# isa_cvx.net
KiCad netlist of a schematic drawn in EAGLE
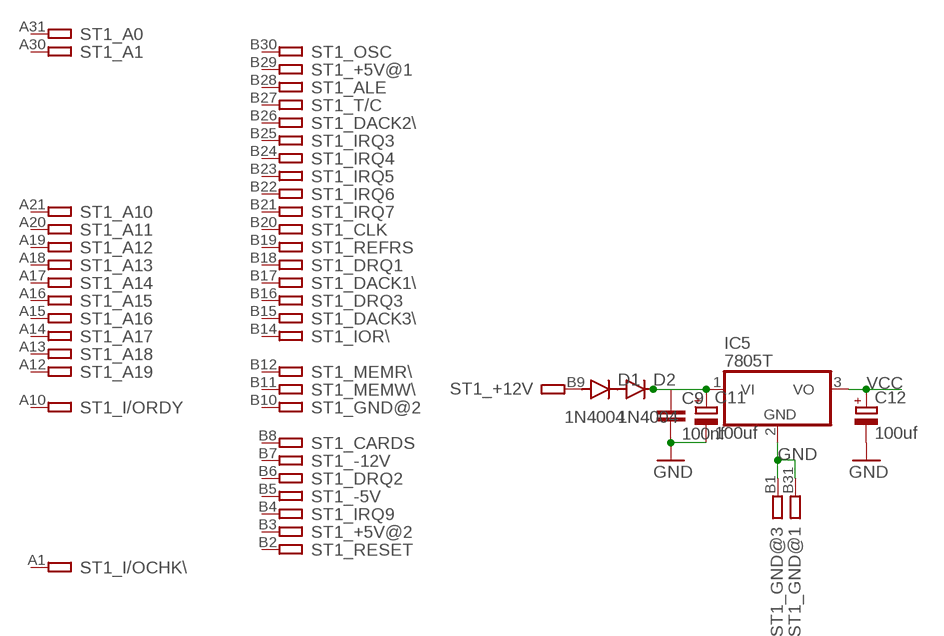
[diagram p0: schematic, sheet 1, part 1 of 2]
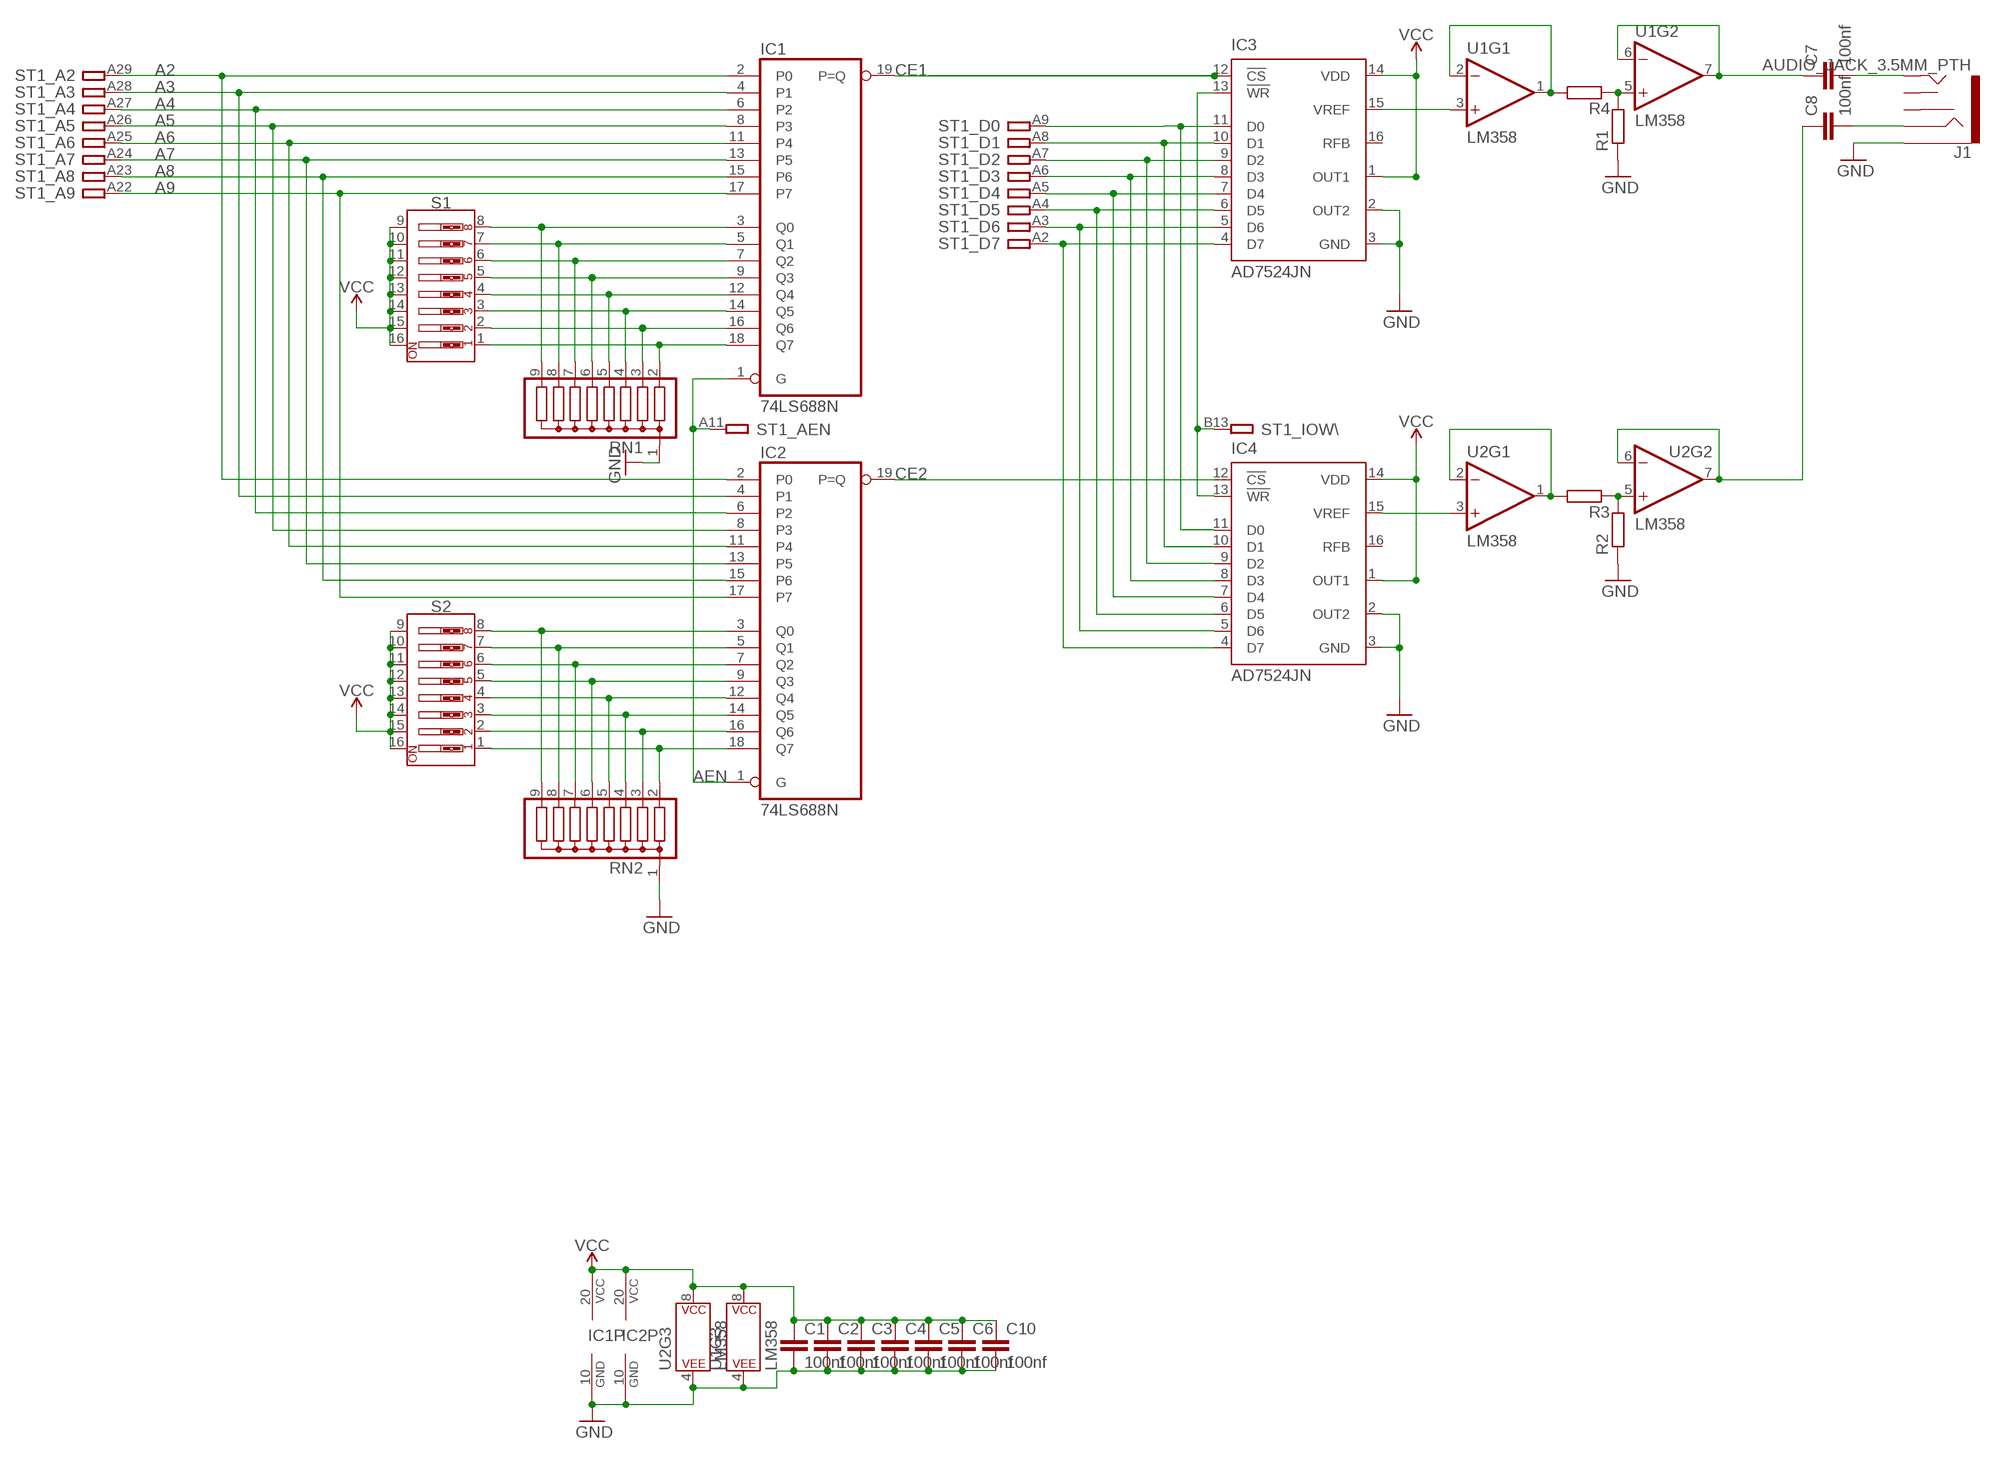
[diagram p1: schematic, sheet 1, part 2 of 2]

(export (version "E")
  (design (tool "Eeschema 10.0.6"))
  (components
    (comp (ref "C1")
      (value "100nf")
      (footprint "eagle-import:C2.5-2")
      (libsource (lib "eagle-import") (part "C2.5/2"))
    )
    (comp (ref "C2")
      (value "100nf")
      (footprint "eagle-import:C2.5-2")
      (libsource (lib "eagle-import") (part "C2.5/2"))
    )
    (comp (ref "C3")
      (value "100nf")
      (footprint "eagle-import:C2.5-2")
      (libsource (lib "eagle-import") (part "C2.5/2"))
    )
    (comp (ref "C4")
      (value "100nf")
      (footprint "eagle-import:C2.5-2")
      (libsource (lib "eagle-import") (part "C2.5/2"))
    )
    (comp (ref "C5")
      (value "100nf")
      (footprint "eagle-import:C2.5-2")
      (libsource (lib "eagle-import") (part "C2.5/2"))
    )
    (comp (ref "C6")
      (value "100nf")
      (footprint "eagle-import:C2.5-2")
      (libsource (lib "eagle-import") (part "C2.5/2"))
    )
    (comp (ref "C7")
      (value "100nf")
      (footprint "eagle-import:C2.5-2")
      (libsource (lib "eagle-import") (part "C2.5/2"))
    )
    (comp (ref "C8")
      (value "100nf")
      (footprint "eagle-import:C2.5-2")
      (libsource (lib "eagle-import") (part "C2.5/2"))
    )
    (comp (ref "C9")
      (value "100nf")
      (footprint "eagle-import:C2.5-2")
      (libsource (lib "eagle-import") (part "C2.5/2"))
    )
    (comp (ref "C10")
      (value "100nf")
      (footprint "eagle-import:C2.5-2")
      (libsource (lib "eagle-import") (part "C2.5/2"))
    )
    (comp (ref "C11")
      (value "100uf")
      (footprint "eagle-import:E2,5-5")
      (libsource (lib "eagle-import") (part "CPOL-EUE2.5-5"))
    )
    (comp (ref "C12")
      (value "100uf")
      (footprint "eagle-import:E2,5-5")
      (libsource (lib "eagle-import") (part "CPOL-EUE2.5-5"))
    )
    (comp (ref "D1")
      (value "1N4004")
      (footprint "eagle-import:DO41-10")
      (libsource (lib "eagle-import") (part "1N4004"))
    )
    (comp (ref "D2")
      (value "1N4004")
      (footprint "eagle-import:DO41-10")
      (libsource (lib "eagle-import") (part "1N4004"))
    )
    (comp (ref "IC1")
      (value "74LS688N")
      (footprint "eagle-import:DIL20")
      (libsource (lib "eagle-import") (part "74688NLS"))
    )
    (comp (ref "IC2")
      (value "74LS688N")
      (footprint "eagle-import:DIL20")
      (libsource (lib "eagle-import") (part "74688NLS"))
    )
    (comp (ref "IC3")
      (value "AD7524JN")
      (footprint "eagle-import:DIL16")
      (fields (field (name "MF") "ALTERA CORPORATION") (field (name "MPN") "AD7524JNZ"))
      (libsource (lib "eagle-import") (part "AD7524NJ"))
    )
    (comp (ref "IC4")
      (value "AD7524JN")
      (footprint "eagle-import:DIL16")
      (fields (field (name "MF") "ALTERA CORPORATION") (field (name "MPN") "AD7524JNZ"))
      (libsource (lib "eagle-import") (part "AD7524NJ"))
    )
    (comp (ref "IC5")
      (value "7805T")
      (footprint "eagle-import:TO220H")
      (libsource (lib "eagle-import") (part "78T05"))
    )
    (comp (ref "J1")
      (value "AUDIO_JACK_3.5MM_PTH")
      (footprint "eagle-import:AUDIO-JACK")
      (libsource (lib "eagle-import") (part "AUDIO_JACK_3.5MM_PTH"))
    )
    (comp (ref "R1")
      (value "R-EU_0207/10")
      (footprint "eagle-import:0207_10")
      (libsource (lib "eagle-import") (part "R-EU_0207/10"))
    )
    (comp (ref "R2")
      (value "R-EU_0207/10")
      (footprint "eagle-import:0207_10")
      (libsource (lib "eagle-import") (part "R-EU_0207/10"))
    )
    (comp (ref "R3")
      (value "R-EU_0207/10")
      (footprint "eagle-import:0207_10")
      (libsource (lib "eagle-import") (part "R-EU_0207/10"))
    )
    (comp (ref "R4")
      (value "R-EU_0207/10")
      (footprint "eagle-import:0207_10")
      (libsource (lib "eagle-import") (part "R-EU_0207/10"))
    )
    (comp (ref "RN1")
      (value "G08R")
      (footprint "eagle-import:SIL9")
      (libsource (lib "eagle-import") (part "G08R"))
    )
    (comp (ref "RN2")
      (value "G08R")
      (footprint "eagle-import:SIL9")
      (libsource (lib "eagle-import") (part "G08R"))
    )
    (comp (ref "S1")
      (value "DIP-08-PTH")
      (footprint "eagle-import:DIPSWITCH-08")
      (libsource (lib "eagle-import") (part "DIP-08-PTH"))
    )
    (comp (ref "S2")
      (value "DIP-08-PTH")
      (footprint "eagle-import:DIPSWITCH-08")
      (libsource (lib "eagle-import") (part "DIP-08-PTH"))
    )
    (comp (ref "ST1")
      (value "IBM8BIT")
      (footprint "eagle-import:IBM8BIT")
      (libsource (lib "eagle-import") (part "IBM8BIT"))
    )
    (comp (ref "U1")
      (value "LM358")
      (footprint "eagle-import:DIP08")
      (libsource (lib "eagle-import") (part "LM358"))
    )
    (comp (ref "U2")
      (value "LM358")
      (footprint "eagle-import:DIP08")
      (libsource (lib "eagle-import") (part "LM358"))
    )
  )
  (nets
    (net (code "1") (name "/A2") (class "Default")
      (node (ref "IC1") (pin "2") (pinfunction "P0_2") (pintype "input"))
      (node (ref "IC2") (pin "2") (pinfunction "P0_2") (pintype "input"))
      (node (ref "ST1") (pin "A29") (pinfunction "P_A29") (pintype "bidirectional"))
    )
    (net (code "2") (name "/A3") (class "Default")
      (node (ref "IC1") (pin "4") (pinfunction "P1_4") (pintype "input"))
      (node (ref "IC2") (pin "4") (pinfunction "P1_4") (pintype "input"))
      (node (ref "ST1") (pin "A28") (pinfunction "P_A28") (pintype "bidirectional"))
    )
    (net (code "3") (name "/A4") (class "Default")
      (node (ref "IC1") (pin "6") (pinfunction "P2_6") (pintype "input"))
      (node (ref "IC2") (pin "6") (pinfunction "P2_6") (pintype "input"))
      (node (ref "ST1") (pin "A27") (pinfunction "P_A27") (pintype "bidirectional"))
    )
    (net (code "4") (name "/A5") (class "Default")
      (node (ref "IC1") (pin "8") (pinfunction "P3_8") (pintype "input"))
      (node (ref "IC2") (pin "8") (pinfunction "P3_8") (pintype "input"))
      (node (ref "ST1") (pin "A26") (pinfunction "P_A26") (pintype "bidirectional"))
    )
    (net (code "5") (name "/A6") (class "Default")
      (node (ref "IC1") (pin "11") (pinfunction "P4_11") (pintype "input"))
      (node (ref "IC2") (pin "11") (pinfunction "P4_11") (pintype "input"))
      (node (ref "ST1") (pin "A25") (pinfunction "P_A25") (pintype "bidirectional"))
    )
    (net (code "6") (name "/A7") (class "Default")
      (node (ref "IC1") (pin "13") (pinfunction "P5_13") (pintype "input"))
      (node (ref "IC2") (pin "13") (pinfunction "P5_13") (pintype "input"))
      (node (ref "ST1") (pin "A24") (pinfunction "P_A24") (pintype "bidirectional"))
    )
    (net (code "7") (name "/A8") (class "Default")
      (node (ref "IC1") (pin "15") (pinfunction "P6_15") (pintype "input"))
      (node (ref "IC2") (pin "15") (pinfunction "P6_15") (pintype "input"))
      (node (ref "ST1") (pin "A23") (pinfunction "P_A23") (pintype "bidirectional"))
    )
    (net (code "8") (name "/A9") (class "Default")
      (node (ref "IC1") (pin "17") (pinfunction "P7_17") (pintype "input"))
      (node (ref "IC2") (pin "17") (pinfunction "P7_17") (pintype "input"))
      (node (ref "ST1") (pin "A22") (pinfunction "P_A22") (pintype "bidirectional"))
    )
    (net (code "9") (name "/AEN") (class "Default")
      (node (ref "IC1") (pin "1") (pinfunction "G_1") (pintype "input"))
      (node (ref "IC2") (pin "1") (pinfunction "G_1") (pintype "input"))
      (node (ref "ST1") (pin "A11") (pinfunction "P_A11") (pintype "bidirectional"))
    )
    (net (code "10") (name "/CE1") (class "Default")
      (node (ref "IC1") (pin "19") (pinfunction "P=Q_19") (pintype "output"))
      (node (ref "IC3") (pin "12") (pinfunction "~{CS}_12") (pintype "input"))
    )
    (net (code "11") (name "/CE2") (class "Default")
      (node (ref "IC2") (pin "19") (pinfunction "P=Q_19") (pintype "output"))
      (node (ref "IC4") (pin "12") (pinfunction "~{CS}_12") (pintype "input"))
    )
    (net (code "12") (name "GND") (class "Default")
      (node (ref "C1") (pin "2") (pinfunction "2_2") (pintype "passive"))
      (node (ref "C10") (pin "2") (pinfunction "2_2") (pintype "passive"))
      (node (ref "C11") (pin "-") (pinfunction "-_-") (pintype "passive"))
      (node (ref "C12") (pin "-") (pinfunction "-_-") (pintype "passive"))
      (node (ref "C2") (pin "2") (pinfunction "2_2") (pintype "passive"))
      (node (ref "C3") (pin "2") (pinfunction "2_2") (pintype "passive"))
      (node (ref "C4") (pin "2") (pinfunction "2_2") (pintype "passive"))
      (node (ref "C5") (pin "2") (pinfunction "2_2") (pintype "passive"))
      (node (ref "C6") (pin "2") (pinfunction "2_2") (pintype "passive"))
      (node (ref "C9") (pin "2") (pinfunction "2_2") (pintype "passive"))
      (node (ref "IC1") (pin "10") (pinfunction "GND_10") (pintype "power_in"))
      (node (ref "IC2") (pin "10") (pinfunction "GND_10") (pintype "power_in"))
      (node (ref "IC3") (pin "2") (pinfunction "OUT2_2") (pintype "passive"))
      (node (ref "IC3") (pin "3") (pinfunction "GND_3") (pintype "power_in"))
      (node (ref "IC4") (pin "2") (pinfunction "OUT2_2") (pintype "passive"))
      (node (ref "IC4") (pin "3") (pinfunction "GND_3") (pintype "power_in"))
      (node (ref "IC5") (pin "2") (pinfunction "GND_2") (pintype "passive"))
      (node (ref "J1") (pin "SLEEVE") (pinfunction "SLEEVE_SLEEVE") (pintype "bidirectional"))
      (node (ref "R1") (pin "1") (pinfunction "1_1") (pintype "passive"))
      (node (ref "R2") (pin "1") (pinfunction "1_1") (pintype "passive"))
      (node (ref "RN1") (pin "1") (pinfunction "1_1") (pintype "passive"))
      (node (ref "RN2") (pin "1") (pinfunction "1_1") (pintype "passive"))
      (node (ref "ST1") (pin "B1") (pinfunction "P_B1") (pintype "bidirectional"))
      (node (ref "ST1") (pin "B31") (pinfunction "P_B31") (pintype "bidirectional"))
      (node (ref "U1") (pin "4") (pinfunction "P$V-_4") (pintype "bidirectional"))
      (node (ref "U2") (pin "4") (pinfunction "P$V-_4") (pintype "bidirectional"))
    )
    (net (code "13") (name "Net-(C7-Pad2)") (class "Default")
      (node (ref "C7") (pin "2") (pinfunction "2_2") (pintype "passive"))
      (node (ref "J1") (pin "TIP") (pinfunction "TIP_TIP") (pintype "bidirectional"))
    )
    (net (code "14") (name "Net-(C8-Pad2)") (class "Default")
      (node (ref "C8") (pin "2") (pinfunction "2_2") (pintype "passive"))
      (node (ref "J1") (pin "RING") (pinfunction "RING_RING") (pintype "bidirectional"))
    )
    (net (code "15") (name "Net-(D1-PadC)") (class "Default")
      (node (ref "D1") (pin "C") (pinfunction "C_C") (pintype "passive"))
      (node (ref "D2") (pin "A") (pinfunction "A_A") (pintype "passive"))
    )
    (net (code "16") (name "Net-(IC1A-Q0)") (class "Default")
      (node (ref "IC1") (pin "3") (pinfunction "Q0_3") (pintype "input"))
      (node (ref "RN1") (pin "9") (pinfunction "9_9") (pintype "passive"))
      (node (ref "S1") (pin "8") (pinfunction "8_8") (pintype "passive"))
    )
    (net (code "17") (name "Net-(IC1A-Q1)") (class "Default")
      (node (ref "IC1") (pin "5") (pinfunction "Q1_5") (pintype "input"))
      (node (ref "RN1") (pin "8") (pinfunction "8_8") (pintype "passive"))
      (node (ref "S1") (pin "7") (pinfunction "7_7") (pintype "passive"))
    )
    (net (code "18") (name "Net-(IC1A-Q2)") (class "Default")
      (node (ref "IC1") (pin "7") (pinfunction "Q2_7") (pintype "input"))
      (node (ref "RN1") (pin "7") (pinfunction "7_7") (pintype "passive"))
      (node (ref "S1") (pin "6") (pinfunction "6_6") (pintype "passive"))
    )
    (net (code "19") (name "Net-(IC1A-Q3)") (class "Default")
      (node (ref "IC1") (pin "9") (pinfunction "Q3_9") (pintype "input"))
      (node (ref "RN1") (pin "6") (pinfunction "6_6") (pintype "passive"))
      (node (ref "S1") (pin "5") (pinfunction "5_5") (pintype "passive"))
    )
    (net (code "20") (name "Net-(IC1A-Q4)") (class "Default")
      (node (ref "IC1") (pin "12") (pinfunction "Q4_12") (pintype "input"))
      (node (ref "RN1") (pin "5") (pinfunction "5_5") (pintype "passive"))
      (node (ref "S1") (pin "4") (pinfunction "4_4") (pintype "passive"))
    )
    (net (code "21") (name "Net-(IC1A-Q5)") (class "Default")
      (node (ref "IC1") (pin "14") (pinfunction "Q5_14") (pintype "input"))
      (node (ref "RN1") (pin "4") (pinfunction "4_4") (pintype "passive"))
      (node (ref "S1") (pin "3") (pinfunction "3_3") (pintype "passive"))
    )
    (net (code "22") (name "Net-(IC1A-Q6)") (class "Default")
      (node (ref "IC1") (pin "16") (pinfunction "Q6_16") (pintype "input"))
      (node (ref "RN1") (pin "3") (pinfunction "3_3") (pintype "passive"))
      (node (ref "S1") (pin "2") (pinfunction "2_2") (pintype "passive"))
    )
    (net (code "23") (name "Net-(IC1A-Q7)") (class "Default")
      (node (ref "IC1") (pin "18") (pinfunction "Q7_18") (pintype "input"))
      (node (ref "RN1") (pin "2") (pinfunction "2_2") (pintype "passive"))
      (node (ref "S1") (pin "1") (pinfunction "1_1") (pintype "passive"))
    )
    (net (code "24") (name "Net-(IC2A-Q0)") (class "Default")
      (node (ref "IC2") (pin "3") (pinfunction "Q0_3") (pintype "input"))
      (node (ref "RN2") (pin "9") (pinfunction "9_9") (pintype "passive"))
      (node (ref "S2") (pin "8") (pinfunction "8_8") (pintype "passive"))
    )
    (net (code "25") (name "Net-(IC2A-Q1)") (class "Default")
      (node (ref "IC2") (pin "5") (pinfunction "Q1_5") (pintype "input"))
      (node (ref "RN2") (pin "8") (pinfunction "8_8") (pintype "passive"))
      (node (ref "S2") (pin "7") (pinfunction "7_7") (pintype "passive"))
    )
    (net (code "26") (name "Net-(IC2A-Q2)") (class "Default")
      (node (ref "IC2") (pin "7") (pinfunction "Q2_7") (pintype "input"))
      (node (ref "RN2") (pin "7") (pinfunction "7_7") (pintype "passive"))
      (node (ref "S2") (pin "6") (pinfunction "6_6") (pintype "passive"))
    )
    (net (code "27") (name "Net-(IC2A-Q3)") (class "Default")
      (node (ref "IC2") (pin "9") (pinfunction "Q3_9") (pintype "input"))
      (node (ref "RN2") (pin "6") (pinfunction "6_6") (pintype "passive"))
      (node (ref "S2") (pin "5") (pinfunction "5_5") (pintype "passive"))
    )
    (net (code "28") (name "Net-(IC2A-Q4)") (class "Default")
      (node (ref "IC2") (pin "12") (pinfunction "Q4_12") (pintype "input"))
      (node (ref "RN2") (pin "5") (pinfunction "5_5") (pintype "passive"))
      (node (ref "S2") (pin "4") (pinfunction "4_4") (pintype "passive"))
    )
    (net (code "29") (name "Net-(IC2A-Q5)") (class "Default")
      (node (ref "IC2") (pin "14") (pinfunction "Q5_14") (pintype "input"))
      (node (ref "RN2") (pin "4") (pinfunction "4_4") (pintype "passive"))
      (node (ref "S2") (pin "3") (pinfunction "3_3") (pintype "passive"))
    )
    (net (code "30") (name "Net-(IC2A-Q6)") (class "Default")
      (node (ref "IC2") (pin "16") (pinfunction "Q6_16") (pintype "input"))
      (node (ref "RN2") (pin "3") (pinfunction "3_3") (pintype "passive"))
      (node (ref "S2") (pin "2") (pinfunction "2_2") (pintype "passive"))
    )
    (net (code "31") (name "Net-(IC2A-Q7)") (class "Default")
      (node (ref "IC2") (pin "18") (pinfunction "Q7_18") (pintype "input"))
      (node (ref "RN2") (pin "2") (pinfunction "2_2") (pintype "passive"))
      (node (ref "S2") (pin "1") (pinfunction "1_1") (pintype "passive"))
    )
    (net (code "32") (name "Net-(IC3-D0)") (class "Default")
      (node (ref "IC3") (pin "11") (pinfunction "D0_11") (pintype "input"))
      (node (ref "IC4") (pin "11") (pinfunction "D0_11") (pintype "input"))
      (node (ref "ST1") (pin "A9") (pinfunction "P_A9") (pintype "bidirectional"))
    )
    (net (code "33") (name "Net-(IC3-D1)") (class "Default")
      (node (ref "IC3") (pin "10") (pinfunction "D1_10") (pintype "input"))
      (node (ref "IC4") (pin "10") (pinfunction "D1_10") (pintype "input"))
      (node (ref "ST1") (pin "A8") (pinfunction "P_A8") (pintype "bidirectional"))
    )
    (net (code "34") (name "Net-(IC3-D2)") (class "Default")
      (node (ref "IC3") (pin "9") (pinfunction "D2_9") (pintype "input"))
      (node (ref "IC4") (pin "9") (pinfunction "D2_9") (pintype "input"))
      (node (ref "ST1") (pin "A7") (pinfunction "P_A7") (pintype "bidirectional"))
    )
    (net (code "35") (name "Net-(IC3-D3)") (class "Default")
      (node (ref "IC3") (pin "8") (pinfunction "D3_8") (pintype "input"))
      (node (ref "IC4") (pin "8") (pinfunction "D3_8") (pintype "input"))
      (node (ref "ST1") (pin "A6") (pinfunction "P_A6") (pintype "bidirectional"))
    )
    (net (code "36") (name "Net-(IC3-D4)") (class "Default")
      (node (ref "IC3") (pin "7") (pinfunction "D4_7") (pintype "input"))
      (node (ref "IC4") (pin "7") (pinfunction "D4_7") (pintype "input"))
      (node (ref "ST1") (pin "A5") (pinfunction "P_A5") (pintype "bidirectional"))
    )
    (net (code "37") (name "Net-(IC3-D5)") (class "Default")
      (node (ref "IC3") (pin "6") (pinfunction "D5_6") (pintype "input"))
      (node (ref "IC4") (pin "6") (pinfunction "D5_6") (pintype "input"))
      (node (ref "ST1") (pin "A4") (pinfunction "P_A4") (pintype "bidirectional"))
    )
    (net (code "38") (name "Net-(IC3-D6)") (class "Default")
      (node (ref "IC3") (pin "5") (pinfunction "D6_5") (pintype "input"))
      (node (ref "IC4") (pin "5") (pinfunction "D6_5") (pintype "input"))
      (node (ref "ST1") (pin "A3") (pinfunction "P_A3") (pintype "bidirectional"))
    )
    (net (code "39") (name "Net-(IC3-D7)") (class "Default")
      (node (ref "IC3") (pin "4") (pinfunction "D7_4") (pintype "input"))
      (node (ref "IC4") (pin "4") (pinfunction "D7_4") (pintype "input"))
      (node (ref "ST1") (pin "A2") (pinfunction "P_A2") (pintype "bidirectional"))
    )
    (net (code "40") (name "Net-(IC3-VREF)") (class "Default")
      (node (ref "IC3") (pin "15") (pinfunction "VREF_15") (pintype "input"))
      (node (ref "U1") (pin "3") (pinfunction "+IN_3") (pintype "input"))
    )
    (net (code "41") (name "Net-(IC3-~{WR})") (class "Default")
      (node (ref "IC3") (pin "13") (pinfunction "~{WR}_13") (pintype "input"))
      (node (ref "IC4") (pin "13") (pinfunction "~{WR}_13") (pintype "input"))
      (node (ref "ST1") (pin "B13") (pinfunction "P_B13") (pintype "bidirectional"))
    )
    (net (code "42") (name "Net-(IC4-VREF)") (class "Default")
      (node (ref "IC4") (pin "15") (pinfunction "VREF_15") (pintype "input"))
      (node (ref "U2") (pin "3") (pinfunction "+IN_3") (pintype "input"))
    )
    (net (code "43") (name "Net-(IC5-VI)") (class "Default")
      (node (ref "C11") (pin "+") (pinfunction "+_+") (pintype "passive"))
      (node (ref "C9") (pin "1") (pinfunction "1_1") (pintype "passive"))
      (node (ref "D2") (pin "C") (pinfunction "C_C") (pintype "passive"))
      (node (ref "IC5") (pin "1") (pinfunction "VI_1") (pintype "input"))
    )
    (net (code "44") (name "Net-(ST1A-P)") (class "Default")
      (node (ref "D1") (pin "A") (pinfunction "A_A") (pintype "passive"))
      (node (ref "ST1") (pin "B9") (pinfunction "P_B9") (pintype "bidirectional"))
    )
    (net (code "45") (name "Net-(U1A--IN)") (class "Default")
      (node (ref "R4") (pin "2") (pinfunction "2_2") (pintype "passive"))
      (node (ref "U1") (pin "1") (pinfunction "OUT_1") (pintype "output"))
      (node (ref "U1") (pin "2") (pinfunction "-IN_2") (pintype "input"))
    )
    (net (code "46") (name "Net-(U1B-+IN)") (class "Default")
      (node (ref "R1") (pin "2") (pinfunction "2_2") (pintype "passive"))
      (node (ref "R4") (pin "1") (pinfunction "1_1") (pintype "passive"))
      (node (ref "U1") (pin "5") (pinfunction "+IN_5") (pintype "input"))
    )
    (net (code "47") (name "Net-(U1B--IN)") (class "Default")
      (node (ref "C7") (pin "1") (pinfunction "1_1") (pintype "passive"))
      (node (ref "U1") (pin "6") (pinfunction "-IN_6") (pintype "input"))
      (node (ref "U1") (pin "7") (pinfunction "OUT_7") (pintype "output"))
    )
    (net (code "48") (name "Net-(U2A--IN)") (class "Default")
      (node (ref "R3") (pin "2") (pinfunction "2_2") (pintype "passive"))
      (node (ref "U2") (pin "1") (pinfunction "OUT_1") (pintype "output"))
      (node (ref "U2") (pin "2") (pinfunction "-IN_2") (pintype "input"))
    )
    (net (code "49") (name "Net-(U2B-+IN)") (class "Default")
      (node (ref "R2") (pin "2") (pinfunction "2_2") (pintype "passive"))
      (node (ref "R3") (pin "1") (pinfunction "1_1") (pintype "passive"))
      (node (ref "U2") (pin "5") (pinfunction "+IN_5") (pintype "input"))
    )
    (net (code "50") (name "Net-(U2B--IN)") (class "Default")
      (node (ref "C8") (pin "1") (pinfunction "1_1") (pintype "passive"))
      (node (ref "U2") (pin "6") (pinfunction "-IN_6") (pintype "input"))
      (node (ref "U2") (pin "7") (pinfunction "OUT_7") (pintype "output"))
    )
    (net (code "51") (name "VCC") (class "Default")
      (node (ref "C1") (pin "1") (pinfunction "1_1") (pintype "passive"))
      (node (ref "C10") (pin "1") (pinfunction "1_1") (pintype "passive"))
      (node (ref "C12") (pin "+") (pinfunction "+_+") (pintype "passive"))
      (node (ref "C2") (pin "1") (pinfunction "1_1") (pintype "passive"))
      (node (ref "C3") (pin "1") (pinfunction "1_1") (pintype "passive"))
      (node (ref "C4") (pin "1") (pinfunction "1_1") (pintype "passive"))
      (node (ref "C5") (pin "1") (pinfunction "1_1") (pintype "passive"))
      (node (ref "C6") (pin "1") (pinfunction "1_1") (pintype "passive"))
      (node (ref "IC1") (pin "20") (pinfunction "VCC_20") (pintype "power_in"))
      (node (ref "IC2") (pin "20") (pinfunction "VCC_20") (pintype "power_in"))
      (node (ref "IC3") (pin "1") (pinfunction "OUT1_1") (pintype "passive"))
      (node (ref "IC3") (pin "14") (pinfunction "VDD_14") (pintype "power_in"))
      (node (ref "IC4") (pin "1") (pinfunction "OUT1_1") (pintype "passive"))
      (node (ref "IC4") (pin "14") (pinfunction "VDD_14") (pintype "power_in"))
      (node (ref "IC5") (pin "3") (pinfunction "VO_3") (pintype "passive"))
      (node (ref "S1") (pin "10") (pinfunction "10_10") (pintype "passive"))
      (node (ref "S1") (pin "11") (pinfunction "11_11") (pintype "passive"))
      (node (ref "S1") (pin "12") (pinfunction "12_12") (pintype "passive"))
      (node (ref "S1") (pin "13") (pinfunction "13_13") (pintype "passive"))
      (node (ref "S1") (pin "14") (pinfunction "14_14") (pintype "passive"))
      (node (ref "S1") (pin "15") (pinfunction "15_15") (pintype "passive"))
      (node (ref "S1") (pin "16") (pinfunction "16_16") (pintype "passive"))
      (node (ref "S1") (pin "9") (pinfunction "9_9") (pintype "passive"))
      (node (ref "S2") (pin "10") (pinfunction "10_10") (pintype "passive"))
      (node (ref "S2") (pin "11") (pinfunction "11_11") (pintype "passive"))
      (node (ref "S2") (pin "12") (pinfunction "12_12") (pintype "passive"))
      (node (ref "S2") (pin "13") (pinfunction "13_13") (pintype "passive"))
      (node (ref "S2") (pin "14") (pinfunction "14_14") (pintype "passive"))
      (node (ref "S2") (pin "15") (pinfunction "15_15") (pintype "passive"))
      (node (ref "S2") (pin "16") (pinfunction "16_16") (pintype "passive"))
      (node (ref "S2") (pin "9") (pinfunction "9_9") (pintype "passive"))
      (node (ref "U1") (pin "8") (pinfunction "P$V+_8") (pintype "bidirectional"))
      (node (ref "U2") (pin "8") (pinfunction "P$V+_8") (pintype "bidirectional"))
    )
    (net (code "52") (name "unconnected-(IC3-RFB-Pad16)") (class "Default")
      (node (ref "IC3") (pin "16") (pinfunction "RFB_16") (pintype "passive"))
    )
    (net (code "53") (name "unconnected-(IC4-RFB-Pad16)") (class "Default")
      (node (ref "IC4") (pin "16") (pinfunction "RFB_16") (pintype "passive"))
    )
    (net (code "54") (name "unconnected-(J1-PadRSH)") (class "Default")
      (node (ref "J1") (pin "RSH") (pinfunction "RSH_RSH") (pintype "bidirectional"))
    )
    (net (code "55") (name "unconnected-(J1-PadTSH)") (class "Default")
      (node (ref "J1") (pin "TSH") (pinfunction "TSH_TSH") (pintype "bidirectional"))
    )
    (net (code "56") (name "unconnected-(ST1AA-P-PadB28)") (class "Default")
      (node (ref "ST1") (pin "B28") (pinfunction "P_B28") (pintype "bidirectional"))
    )
    (net (code "57") (name "unconnected-(ST1AB-P-PadB8)") (class "Default")
      (node (ref "ST1") (pin "B8") (pinfunction "P_B8") (pintype "bidirectional"))
    )
    (net (code "58") (name "unconnected-(ST1AC-P-PadB20)") (class "Default")
      (node (ref "ST1") (pin "B20") (pinfunction "P_B20") (pintype "bidirectional"))
    )
    (net (code "59") (name "unconnected-(ST1AL-P-PadB17)") (class "Default")
      (node (ref "ST1") (pin "B17") (pinfunction "P_B17") (pintype "bidirectional"))
    )
    (net (code "60") (name "unconnected-(ST1AM-P-PadB26)") (class "Default")
      (node (ref "ST1") (pin "B26") (pinfunction "P_B26") (pintype "bidirectional"))
    )
    (net (code "61") (name "unconnected-(ST1AN-P-PadB15)") (class "Default")
      (node (ref "ST1") (pin "B15") (pinfunction "P_B15") (pintype "bidirectional"))
    )
    (net (code "62") (name "unconnected-(ST1AO-P-PadB18)") (class "Default")
      (node (ref "ST1") (pin "B18") (pinfunction "P_B18") (pintype "bidirectional"))
    )
    (net (code "63") (name "unconnected-(ST1AP-P-PadB6)") (class "Default")
      (node (ref "ST1") (pin "B6") (pinfunction "P_B6") (pintype "bidirectional"))
    )
    (net (code "64") (name "unconnected-(ST1AQ-P-PadB16)") (class "Default")
      (node (ref "ST1") (pin "B16") (pinfunction "P_B16") (pintype "bidirectional"))
    )
    (net (code "65") (name "unconnected-(ST1AS-P-PadB10)") (class "Default")
      (node (ref "ST1") (pin "B10") (pinfunction "P_B10") (pintype "bidirectional"))
    )
    (net (code "66") (name "unconnected-(ST1AU-P-PadA1)") (class "Default")
      (node (ref "ST1") (pin "A1") (pinfunction "P_A1") (pintype "bidirectional"))
    )
    (net (code "67") (name "unconnected-(ST1AV-P-PadA10)") (class "Default")
      (node (ref "ST1") (pin "A10") (pinfunction "P_A10") (pintype "bidirectional"))
    )
    (net (code "68") (name "unconnected-(ST1AW-P-PadB14)") (class "Default")
      (node (ref "ST1") (pin "B14") (pinfunction "P_B14") (pintype "bidirectional"))
    )
    (net (code "69") (name "unconnected-(ST1AY-P-PadB25)") (class "Default")
      (node (ref "ST1") (pin "B25") (pinfunction "P_B25") (pintype "bidirectional"))
    )
    (net (code "70") (name "unconnected-(ST1AZ-P-PadB24)") (class "Default")
      (node (ref "ST1") (pin "B24") (pinfunction "P_B24") (pintype "bidirectional"))
    )
    (net (code "71") (name "unconnected-(ST1B-P-PadB29)") (class "Default")
      (node (ref "ST1") (pin "B29") (pinfunction "P_B29") (pintype "bidirectional"))
    )
    (net (code "72") (name "unconnected-(ST1BA-P-PadB23)") (class "Default")
      (node (ref "ST1") (pin "B23") (pinfunction "P_B23") (pintype "bidirectional"))
    )
    (net (code "73") (name "unconnected-(ST1BB-P-PadB22)") (class "Default")
      (node (ref "ST1") (pin "B22") (pinfunction "P_B22") (pintype "bidirectional"))
    )
    (net (code "74") (name "unconnected-(ST1BC-P-PadB21)") (class "Default")
      (node (ref "ST1") (pin "B21") (pinfunction "P_B21") (pintype "bidirectional"))
    )
    (net (code "75") (name "unconnected-(ST1BD-P-PadB4)") (class "Default")
      (node (ref "ST1") (pin "B4") (pinfunction "P_B4") (pintype "bidirectional"))
    )
    (net (code "76") (name "unconnected-(ST1BE-P-PadB12)") (class "Default")
      (node (ref "ST1") (pin "B12") (pinfunction "P_B12") (pintype "bidirectional"))
    )
    (net (code "77") (name "unconnected-(ST1BF-P-PadB11)") (class "Default")
      (node (ref "ST1") (pin "B11") (pinfunction "P_B11") (pintype "bidirectional"))
    )
    (net (code "78") (name "unconnected-(ST1BG-P-PadB30)") (class "Default")
      (node (ref "ST1") (pin "B30") (pinfunction "P_B30") (pintype "bidirectional"))
    )
    (net (code "79") (name "unconnected-(ST1BH-P-PadB19)") (class "Default")
      (node (ref "ST1") (pin "B19") (pinfunction "P_B19") (pintype "bidirectional"))
    )
    (net (code "80") (name "unconnected-(ST1BI-P-PadB2)") (class "Default")
      (node (ref "ST1") (pin "B2") (pinfunction "P_B2") (pintype "bidirectional"))
    )
    (net (code "81") (name "unconnected-(ST1BJ-P-PadB27)") (class "Default")
      (node (ref "ST1") (pin "B27") (pinfunction "P_B27") (pintype "bidirectional"))
    )
    (net (code "82") (name "unconnected-(ST1C-P-PadB3)") (class "Default")
      (node (ref "ST1") (pin "B3") (pinfunction "P_B3") (pintype "bidirectional"))
    )
    (net (code "83") (name "unconnected-(ST1D-P-PadB7)") (class "Default")
      (node (ref "ST1") (pin "B7") (pinfunction "P_B7") (pintype "bidirectional"))
    )
    (net (code "84") (name "unconnected-(ST1E-P-PadB5)") (class "Default")
      (node (ref "ST1") (pin "B5") (pinfunction "P_B5") (pintype "bidirectional"))
    )
    (net (code "85") (name "unconnected-(ST1F-P-PadA31)") (class "Default")
      (node (ref "ST1") (pin "A31") (pinfunction "P_A31") (pintype "bidirectional"))
    )
    (net (code "86") (name "unconnected-(ST1G-P-PadA30)") (class "Default")
      (node (ref "ST1") (pin "A30") (pinfunction "P_A30") (pintype "bidirectional"))
    )
    (net (code "87") (name "unconnected-(ST1H-P-PadA21)") (class "Default")
      (node (ref "ST1") (pin "A21") (pinfunction "P_A21") (pintype "bidirectional"))
    )
    (net (code "88") (name "unconnected-(ST1I-P-PadA20)") (class "Default")
      (node (ref "ST1") (pin "A20") (pinfunction "P_A20") (pintype "bidirectional"))
    )
    (net (code "89") (name "unconnected-(ST1J-P-PadA19)") (class "Default")
      (node (ref "ST1") (pin "A19") (pinfunction "P_A19") (pintype "bidirectional"))
    )
    (net (code "90") (name "unconnected-(ST1K-P-PadA18)") (class "Default")
      (node (ref "ST1") (pin "A18") (pinfunction "P_A18") (pintype "bidirectional"))
    )
    (net (code "91") (name "unconnected-(ST1L-P-PadA17)") (class "Default")
      (node (ref "ST1") (pin "A17") (pinfunction "P_A17") (pintype "bidirectional"))
    )
    (net (code "92") (name "unconnected-(ST1M-P-PadA16)") (class "Default")
      (node (ref "ST1") (pin "A16") (pinfunction "P_A16") (pintype "bidirectional"))
    )
    (net (code "93") (name "unconnected-(ST1N-P-PadA15)") (class "Default")
      (node (ref "ST1") (pin "A15") (pinfunction "P_A15") (pintype "bidirectional"))
    )
    (net (code "94") (name "unconnected-(ST1O-P-PadA14)") (class "Default")
      (node (ref "ST1") (pin "A14") (pinfunction "P_A14") (pintype "bidirectional"))
    )
    (net (code "95") (name "unconnected-(ST1P-P-PadA13)") (class "Default")
      (node (ref "ST1") (pin "A13") (pinfunction "P_A13") (pintype "bidirectional"))
    )
    (net (code "96") (name "unconnected-(ST1Q-P-PadA12)") (class "Default")
      (node (ref "ST1") (pin "A12") (pinfunction "P_A12") (pintype "bidirectional"))
    )
  )
)
